# riffle-base-test.net
KiCad netlist of a schematic drawn in EAGLE
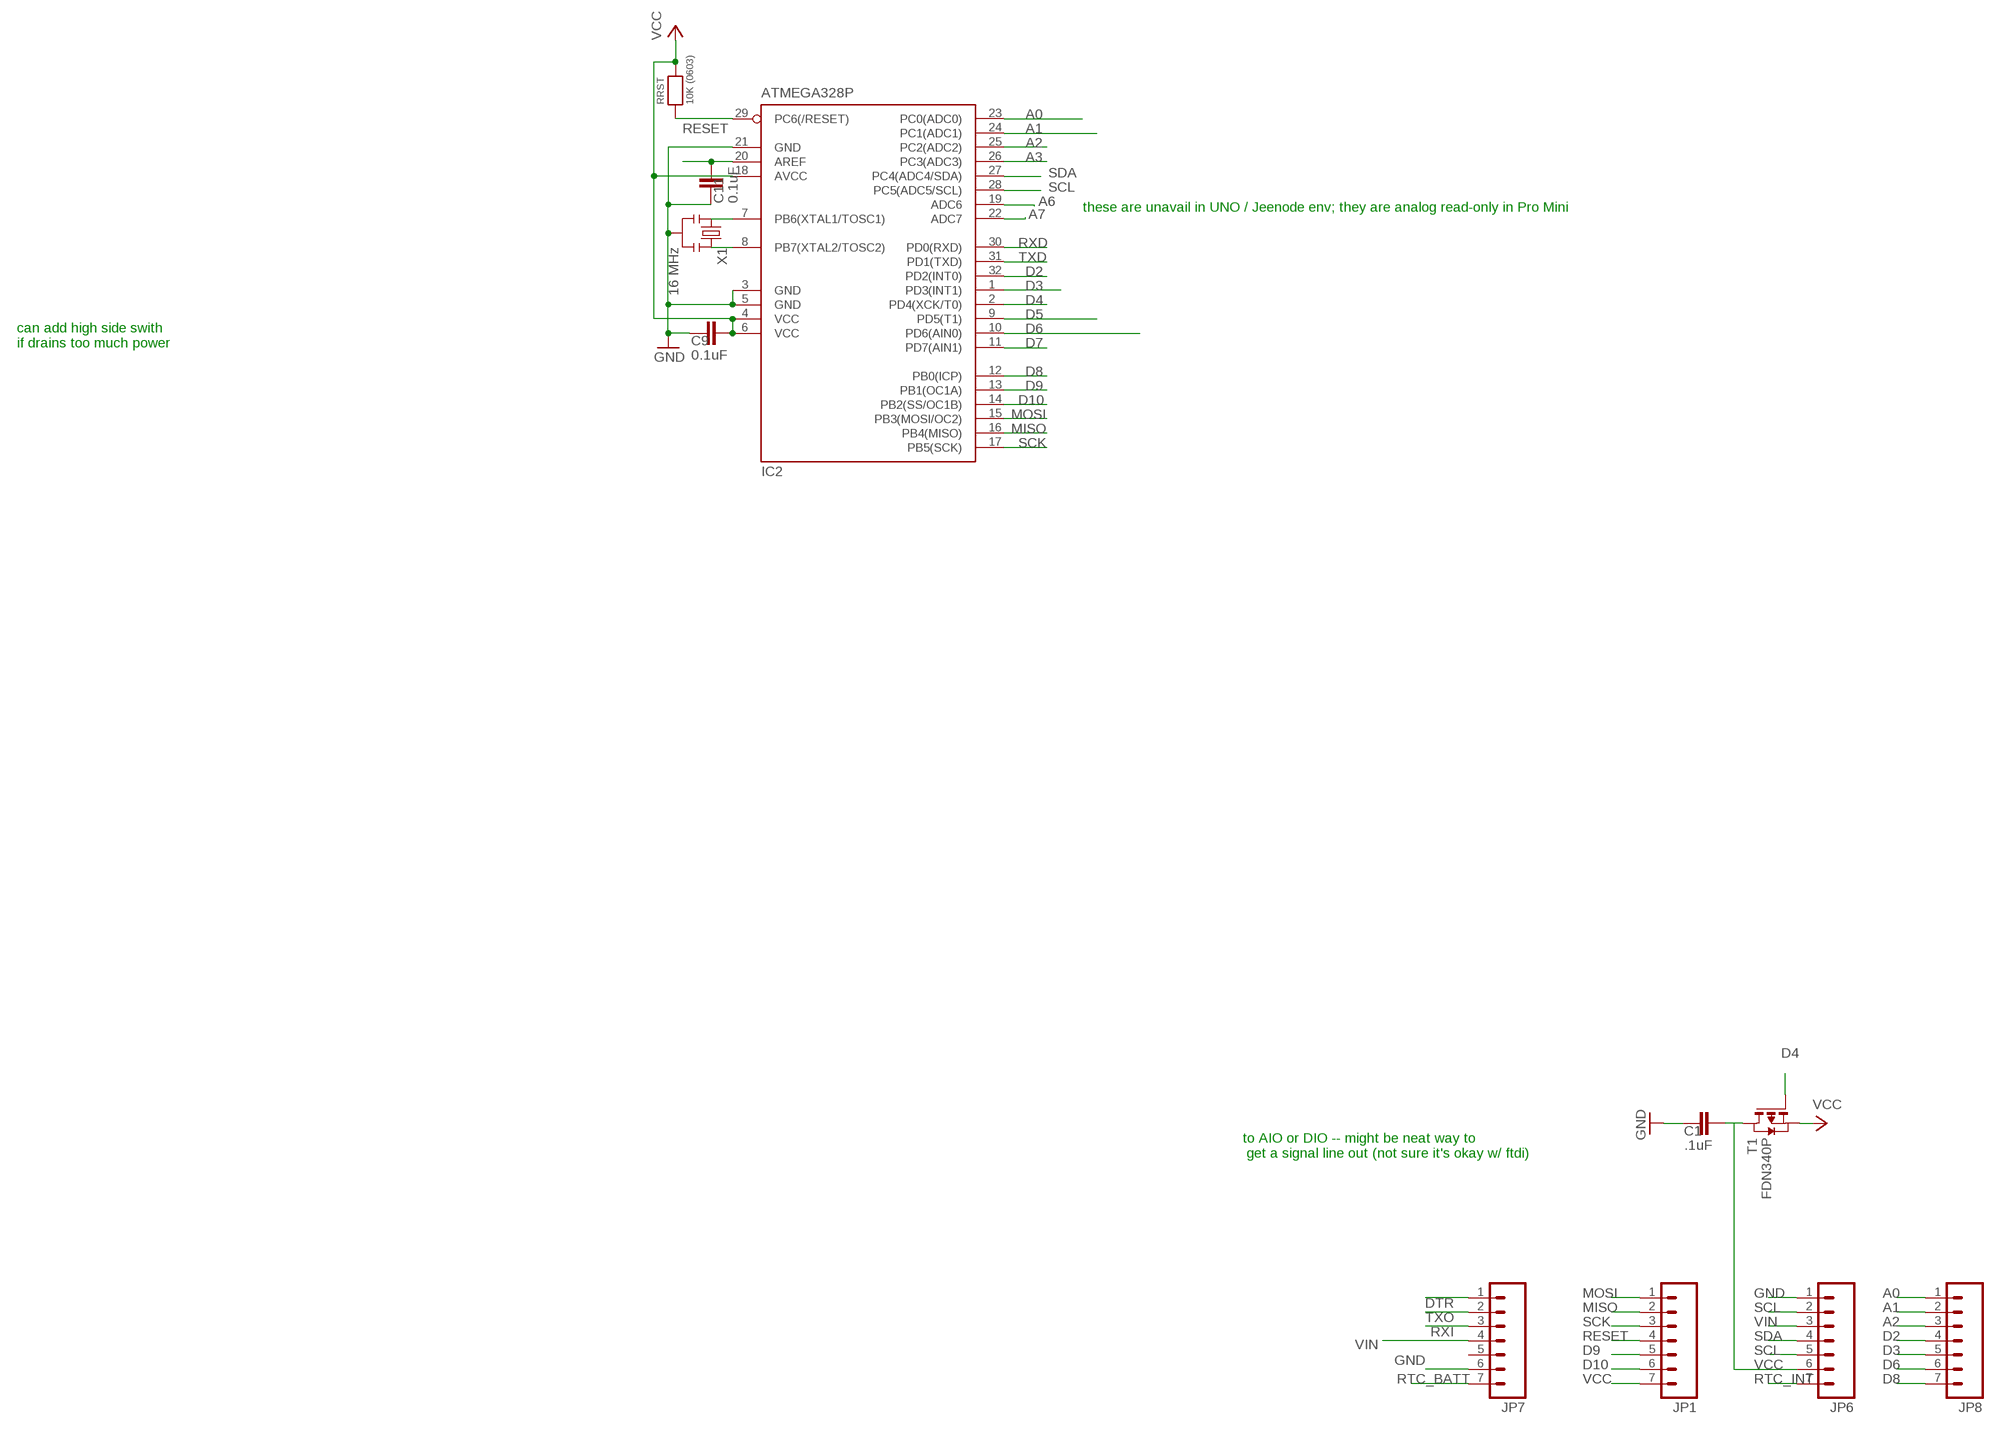
[diagram p0: schematic, sheet 1]

(export (version "E")
  (design (tool "Eeschema 10.0.6"))
  (components
    (comp (ref "C1")
      (value ".1uF")
      (footprint "eagle-import:C0805@1")
      (libsource (lib "eagle-import") (part "C-EUC0805"))
    )
    (comp (ref "C9")
      (value "0.1uF")
      (footprint "eagle-import:C0805@1")
      (libsource (lib "eagle-import") (part "C-EUC0805"))
    )
    (comp (ref "C11")
      (value "0.1uF")
      (footprint "eagle-import:C0805@1")
      (libsource (lib "eagle-import") (part "C-EUC0805"))
    )
    (comp (ref "IC2")
      (value "ATMEGA328P")
      (footprint "eagle-import:TQFP32-08")
      (fields (field (name "MPN") "ATMEGA8-16AU"))
      (libsource (lib "eagle-import") (part "MEGA8-AI"))
    )
    (comp (ref "JP1")
      (value "M07")
      (footprint "eagle-import:1X07")
      (libsource (lib "eagle-import") (part "M07"))
    )
    (comp (ref "JP6")
      (value "M07")
      (footprint "eagle-import:1X07")
      (libsource (lib "eagle-import") (part "M07"))
    )
    (comp (ref "JP7")
      (value "M07")
      (footprint "eagle-import:1X07")
      (libsource (lib "eagle-import") (part "M07"))
    )
    (comp (ref "JP8")
      (value "M07")
      (footprint "eagle-import:1X07")
      (libsource (lib "eagle-import") (part "M07"))
    )
    (comp (ref "RRST")
      (value "10K (0603)")
      (footprint "eagle-import:0603-NO")
      (libsource (lib "eagle-import") (part "RESISTOR_0603_NOOUT"))
    )
    (comp (ref "T1")
      (value "FDN340P")
      (footprint "eagle-import:SOT-23")
      (libsource (lib "eagle-import") (part "PMOSSOT23"))
    )
    (comp (ref "X1")
      (value "16 MHz")
      (footprint "eagle-import:RESONATOR-SMD")
      (libsource (lib "eagle-import") (part "RESONATORSMD"))
    )
  )
  (nets
    (net (code "1") (name "/A0") (class "Default")
      (node (ref "IC2") (pin "23") (pinfunction "PC0(ADC0)_23") (pintype "bidirectional"))
      (node (ref "JP8") (pin "1") (pinfunction "1_1") (pintype "passive"))
    )
    (net (code "2") (name "/A1") (class "Default")
      (node (ref "IC2") (pin "24") (pinfunction "PC1(ADC1)_24") (pintype "bidirectional"))
      (node (ref "JP8") (pin "2") (pinfunction "2_2") (pintype "passive"))
    )
    (net (code "3") (name "/A2") (class "Default")
      (node (ref "IC2") (pin "25") (pinfunction "PC2(ADC2)_25") (pintype "bidirectional"))
      (node (ref "JP8") (pin "3") (pinfunction "3_3") (pintype "passive"))
    )
    (net (code "4") (name "/A3") (class "Default")
      (node (ref "IC2") (pin "26") (pinfunction "PC3(ADC3)_26") (pintype "bidirectional"))
    )
    (net (code "5") (name "/A6") (class "Default")
      (node (ref "IC2") (pin "19") (pinfunction "ADC6_19") (pintype "bidirectional"))
    )
    (net (code "6") (name "/A7") (class "Default")
      (node (ref "IC2") (pin "22") (pinfunction "ADC7_22") (pintype "bidirectional"))
    )
    (net (code "7") (name "/D2") (class "Default")
      (node (ref "IC2") (pin "32") (pinfunction "PD2(INT0)_32") (pintype "bidirectional"))
      (node (ref "JP8") (pin "4") (pinfunction "4_4") (pintype "passive"))
    )
    (net (code "8") (name "/D3") (class "Default")
      (node (ref "IC2") (pin "1") (pinfunction "PD3(INT1)_1") (pintype "bidirectional"))
      (node (ref "JP8") (pin "5") (pinfunction "5_5") (pintype "passive"))
    )
    (net (code "9") (name "/D4") (class "Default")
      (node (ref "IC2") (pin "2") (pinfunction "PD4(XCK/T0)_2") (pintype "bidirectional"))
      (node (ref "T1") (pin "3") (pinfunction "G_3") (pintype "passive"))
    )
    (net (code "10") (name "/D5") (class "Default")
      (node (ref "IC2") (pin "9") (pinfunction "PD5(T1)_9") (pintype "bidirectional"))
    )
    (net (code "11") (name "/D6") (class "Default")
      (node (ref "IC2") (pin "10") (pinfunction "PD6(AIN0)_10") (pintype "bidirectional"))
      (node (ref "JP8") (pin "6") (pinfunction "6_6") (pintype "passive"))
    )
    (net (code "12") (name "/D7") (class "Default")
      (node (ref "IC2") (pin "11") (pinfunction "PD7(AIN1)_11") (pintype "bidirectional"))
    )
    (net (code "13") (name "/D8") (class "Default")
      (node (ref "IC2") (pin "12") (pinfunction "PB0(ICP)_12") (pintype "bidirectional"))
      (node (ref "JP8") (pin "7") (pinfunction "7_7") (pintype "passive"))
    )
    (net (code "14") (name "/D9") (class "Default")
      (node (ref "IC2") (pin "13") (pinfunction "PB1(OC1A)_13") (pintype "bidirectional"))
      (node (ref "JP1") (pin "5") (pinfunction "5_5") (pintype "passive"))
    )
    (net (code "15") (name "/D10") (class "Default")
      (node (ref "IC2") (pin "14") (pinfunction "PB2(SS/OC1B)_14") (pintype "bidirectional"))
      (node (ref "JP1") (pin "6") (pinfunction "6_6") (pintype "passive"))
    )
    (net (code "16") (name "/DTR") (class "Default")
      (node (ref "JP7") (pin "1") (pinfunction "1_1") (pintype "passive"))
    )
    (net (code "17") (name "/MISO") (class "Default")
      (node (ref "IC2") (pin "16") (pinfunction "PB4(MISO)_16") (pintype "bidirectional"))
      (node (ref "JP1") (pin "2") (pinfunction "2_2") (pintype "passive"))
    )
    (net (code "18") (name "/MOSI") (class "Default")
      (node (ref "IC2") (pin "15") (pinfunction "PB3(MOSI/OC2)_15") (pintype "bidirectional"))
      (node (ref "JP1") (pin "1") (pinfunction "1_1") (pintype "passive"))
    )
    (net (code "19") (name "/RESET") (class "Default")
      (node (ref "IC2") (pin "29") (pinfunction "PC6(/RESET)_29") (pintype "bidirectional"))
      (node (ref "JP1") (pin "4") (pinfunction "4_4") (pintype "passive"))
      (node (ref "RRST") (pin "1") (pinfunction "1_1") (pintype "passive"))
    )
    (net (code "20") (name "/RTC_BATT") (class "Default")
      (node (ref "JP7") (pin "7") (pinfunction "7_7") (pintype "passive"))
    )
    (net (code "21") (name "/RTC_INT") (class "Default")
      (node (ref "JP6") (pin "7") (pinfunction "7_7") (pintype "passive"))
    )
    (net (code "22") (name "/RXD") (class "Default")
      (node (ref "IC2") (pin "30") (pinfunction "PD0(RXD)_30") (pintype "bidirectional"))
    )
    (net (code "23") (name "/RXI") (class "Default")
      (node (ref "JP7") (pin "3") (pinfunction "3_3") (pintype "passive"))
    )
    (net (code "24") (name "/SCK") (class "Default")
      (node (ref "IC2") (pin "17") (pinfunction "PB5(SCK)_17") (pintype "bidirectional"))
      (node (ref "JP1") (pin "3") (pinfunction "3_3") (pintype "passive"))
    )
    (net (code "25") (name "/SCL") (class "Default")
      (node (ref "IC2") (pin "28") (pinfunction "PC5(ADC5/SCL)_28") (pintype "bidirectional"))
      (node (ref "JP6") (pin "2") (pinfunction "2_2") (pintype "passive"))
      (node (ref "JP6") (pin "5") (pinfunction "5_5") (pintype "passive"))
    )
    (net (code "26") (name "/SDA") (class "Default")
      (node (ref "IC2") (pin "27") (pinfunction "PC4(ADC4/SDA)_27") (pintype "bidirectional"))
      (node (ref "JP6") (pin "4") (pinfunction "4_4") (pintype "passive"))
    )
    (net (code "27") (name "/TXD") (class "Default")
      (node (ref "IC2") (pin "31") (pinfunction "PD1(TXD)_31") (pintype "bidirectional"))
    )
    (net (code "28") (name "/TXO") (class "Default")
      (node (ref "JP7") (pin "2") (pinfunction "2_2") (pintype "passive"))
    )
    (net (code "29") (name "/VIN") (class "Default")
      (node (ref "JP6") (pin "3") (pinfunction "3_3") (pintype "passive"))
      (node (ref "JP7") (pin "4") (pinfunction "4_4") (pintype "passive"))
    )
    (net (code "30") (name "GND") (class "Default")
      (node (ref "C1") (pin "1") (pinfunction "1_1") (pintype "passive"))
      (node (ref "C11") (pin "1") (pinfunction "1_1") (pintype "passive"))
      (node (ref "C9") (pin "1") (pinfunction "1_1") (pintype "passive"))
      (node (ref "IC2") (pin "21") (pinfunction "GND_21") (pintype "power_in"))
      (node (ref "IC2") (pin "3") (pinfunction "GND_3") (pintype "power_in"))
      (node (ref "IC2") (pin "5") (pinfunction "GND_5") (pintype "power_in"))
      (node (ref "JP6") (pin "1") (pinfunction "1_1") (pintype "passive"))
      (node (ref "JP7") (pin "6") (pinfunction "6_6") (pintype "passive"))
      (node (ref "X1") (pin "2") (pinfunction "2_2") (pintype "passive"))
    )
    (net (code "31") (name "Net-(IC2-AREF)") (class "Default")
      (node (ref "C11") (pin "2") (pinfunction "2_2") (pintype "passive"))
      (node (ref "IC2") (pin "20") (pinfunction "AREF_20") (pintype "passive"))
    )
    (net (code "32") (name "Net-(IC2-PB6(XTAL1{slash}TOSC1))") (class "Default")
      (node (ref "IC2") (pin "7") (pinfunction "PB6(XTAL1/TOSC1)_7") (pintype "bidirectional"))
      (node (ref "X1") (pin "1") (pinfunction "1_1") (pintype "passive"))
    )
    (net (code "33") (name "Net-(IC2-PB7(XTAL2{slash}TOSC2))") (class "Default")
      (node (ref "IC2") (pin "8") (pinfunction "PB7(XTAL2/TOSC2)_8") (pintype "bidirectional"))
      (node (ref "X1") (pin "3") (pinfunction "3_3") (pintype "passive"))
    )
    (net (code "34") (name "VCC") (class "Default")
      (node (ref "C1") (pin "2") (pinfunction "2_2") (pintype "passive"))
      (node (ref "C9") (pin "2") (pinfunction "2_2") (pintype "passive"))
      (node (ref "IC2") (pin "18") (pinfunction "AVCC_18") (pintype "power_in"))
      (node (ref "IC2") (pin "4") (pinfunction "VCC_4") (pintype "power_in"))
      (node (ref "IC2") (pin "6") (pinfunction "VCC_6") (pintype "power_in"))
      (node (ref "JP1") (pin "7") (pinfunction "7_7") (pintype "passive"))
      (node (ref "JP6") (pin "6") (pinfunction "6_6") (pintype "passive"))
      (node (ref "RRST") (pin "2") (pinfunction "2_2") (pintype "passive"))
      (node (ref "T1") (pin "1") (pinfunction "D_1") (pintype "passive"))
      (node (ref "T1") (pin "2") (pinfunction "S_2") (pintype "passive"))
    )
    (net (code "35") (name "unconnected-(JP7-Pad5)") (class "Default")
      (node (ref "JP7") (pin "5") (pinfunction "5_5") (pintype "passive"))
    )
  )
)
